# compass.net
KiCad netlist of a schematic drawn in EAGLE
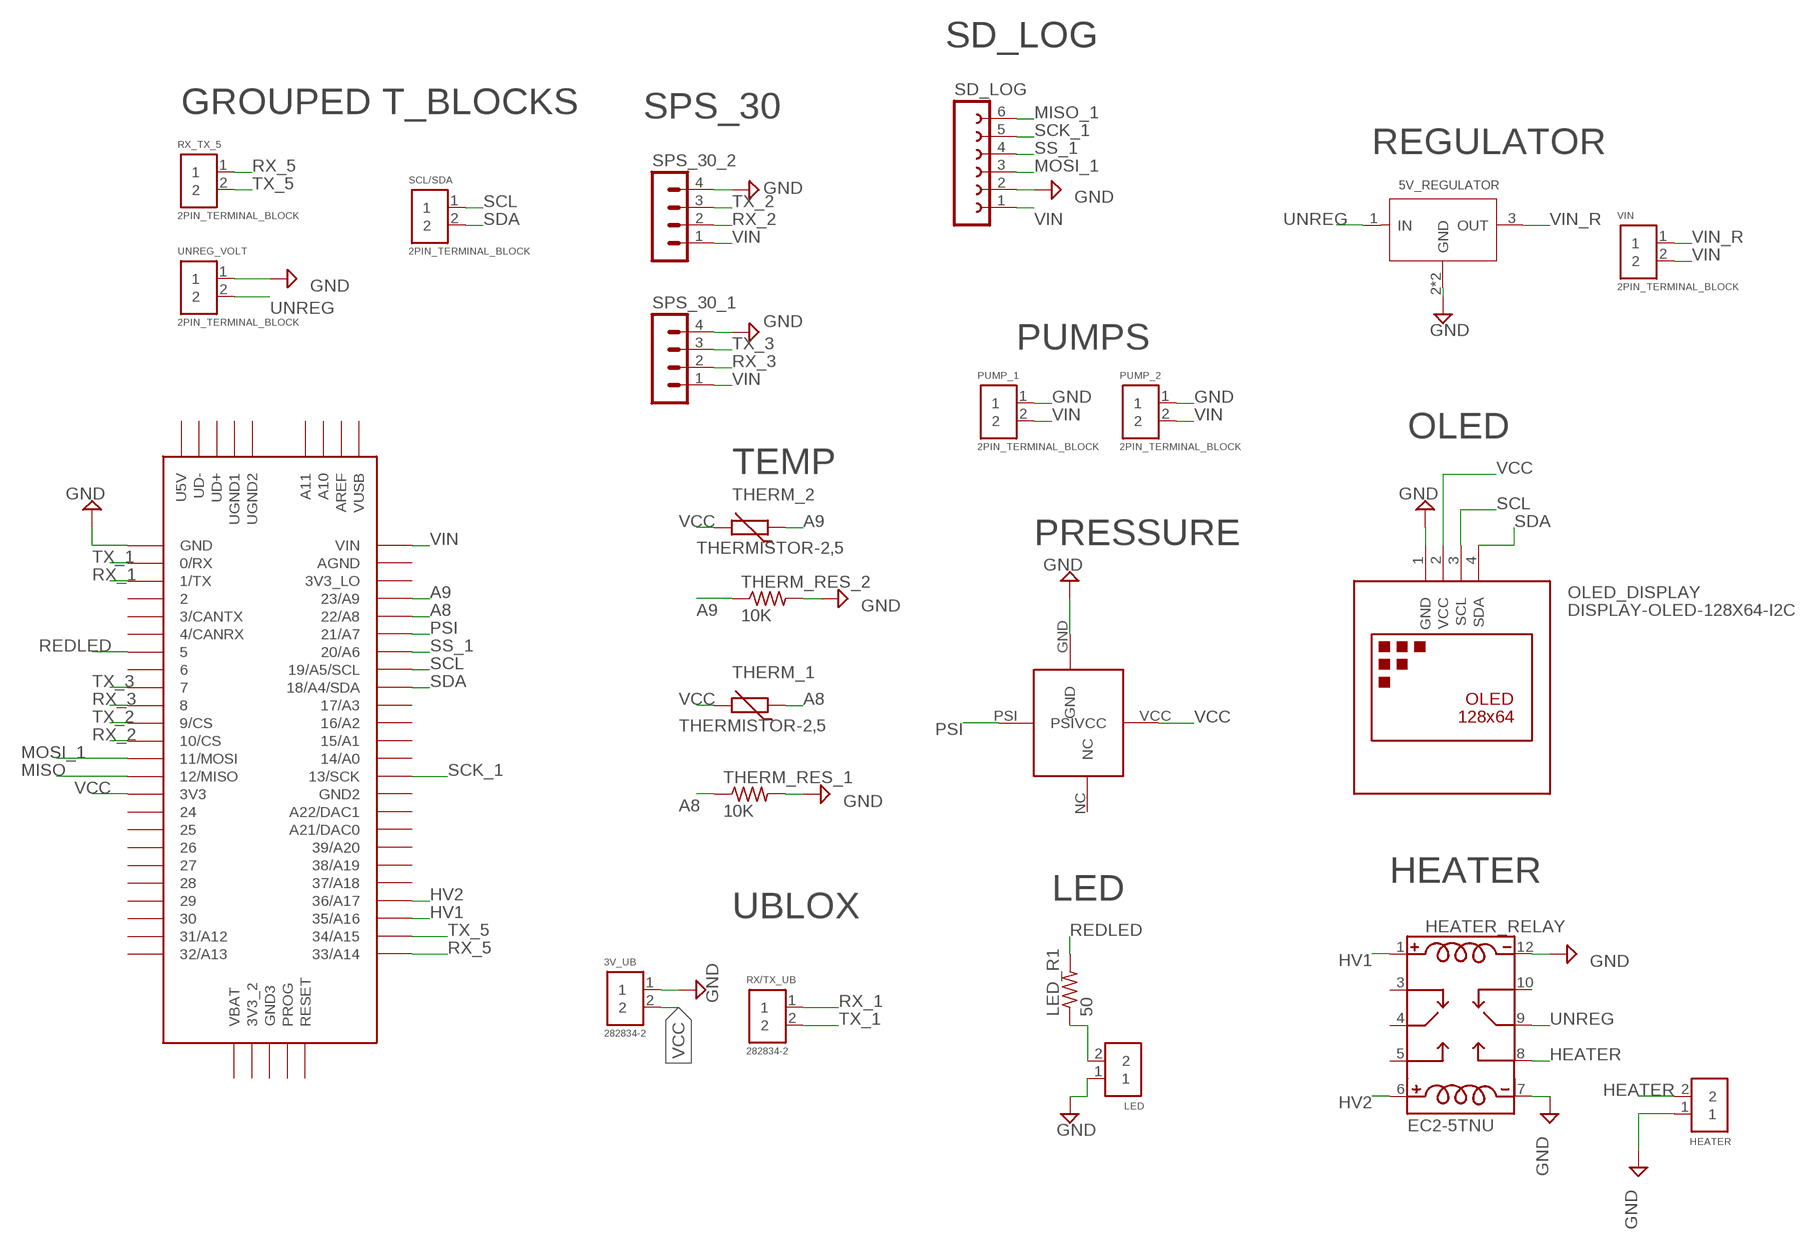
[diagram p0: schematic, sheet 1]

(export (version "E")
  (design (tool "Eeschema 10.0.6"))
  (components
    (comp (ref "3V_UB")
      (value "282834-2")
      (footprint "eagle-import:CONN_282834-2")
      (fields (field (name "DIGI-KEY_PART_NUMBER") "A98333-ND") (field (name "MF") "TE Connectivity"))
      (libsource (lib "eagle-import") (part "282834-2"))
    )
    (comp (ref "5V_REGULATOR")
      (value "PMIC-L7805CV-DG(TO-220)")
      (footprint "eagle-import:TO-220")
      (fields
        (field (name "DIGI-KEY_PART_NUMBER") "497-12404-ND")
        (field (name "MF") "STMicroelectronics")
        (field (name "MP") "L7805CV-DG")
      )
      (libsource (lib "eagle-import") (part "PMIC-L7805CV-DG(TO-220)"))
    )
    (comp (ref "HEATER")
      (value "2PIN_TERMINAL_BLOCK")
      (footprint "eagle-import:2PIN_TERMINAL_BLOCK")
      (fields
        (field (name "COMMENT") "282834-2")
        (field (name "DIGI-KEY_PART_NUMBER") "A98333-ND")
        (field (name "MF") "TE Connectivity")
      )
      (libsource (lib "eagle-import") (part "2PIN_TERMINAL_BLOCK"))
    )
    (comp (ref "HEATER_RELAY")
      (value "EC2-5TNU")
      (footprint "eagle-import:RELAY_EC2-5TNU")
      (fields (field (name "MF") "KEMET"))
      (libsource (lib "eagle-import") (part "EC2-5TNU"))
    )
    (comp (ref "LED")
      (value "282834-2")
      (footprint "eagle-import:CONN_282834-2")
      (fields (field (name "DIGI-KEY_PART_NUMBER") "A98333-ND") (field (name "MF") "TE Connectivity"))
      (libsource (lib "eagle-import") (part "282834-2"))
    )
    (comp (ref "LED_R1")
      (value "50")
      (footprint "eagle-import:0204_7")
      (libsource (lib "eagle-import") (part "resistor_348_R-US_0204/7"))
    )
    (comp (ref "OLED_DISPLAY")
      (value "DISPLAY-OLED-128X64-I2C")
      (footprint "eagle-import:DISPLAY-OLED-128X64-I2C")
      (libsource (lib "eagle-import") (part "DISPLAY-OLED-128X64-I2C"))
    )
    (comp (ref "PRESSURE_SENSOR")
      (value "SSCSANN015PAAA5")
      (footprint "eagle-import:SSCSANN015PAAA5")
      (libsource (lib "eagle-import") (part "SSCSANN015PAAA5"))
    )
    (comp (ref "PUMP_1")
      (value "2PIN_TERMINAL_BLOCK")
      (footprint "eagle-import:2PIN_TERMINAL_BLOCK")
      (fields
        (field (name "COMMENT") "282834-2")
        (field (name "DIGI-KEY_PART_NUMBER") "A98333-ND")
        (field (name "MF") "TE Connectivity")
      )
      (libsource (lib "eagle-import") (part "2PIN_TERMINAL_BLOCK"))
    )
    (comp (ref "PUMP_2")
      (value "2PIN_TERMINAL_BLOCK")
      (footprint "eagle-import:2PIN_TERMINAL_BLOCK")
      (fields
        (field (name "COMMENT") "282834-2")
        (field (name "DIGI-KEY_PART_NUMBER") "A98333-ND")
        (field (name "MF") "TE Connectivity")
      )
      (libsource (lib "eagle-import") (part "2PIN_TERMINAL_BLOCK"))
    )
    (comp (ref "RX/TX_UB")
      (value "282834-2")
      (footprint "eagle-import:CONN_282834-2")
      (fields (field (name "DIGI-KEY_PART_NUMBER") "A98333-ND") (field (name "MF") "TE Connectivity"))
      (libsource (lib "eagle-import") (part "282834-2"))
    )
    (comp (ref "RX_TX_5")
      (value "2PIN_TERMINAL_BLOCK")
      (footprint "eagle-import:2PIN_TERMINAL_BLOCK")
      (fields
        (field (name "COMMENT") "282834-2")
        (field (name "DIGI-KEY_PART_NUMBER") "A98333-ND")
        (field (name "MF") "TE Connectivity")
      )
      (libsource (lib "eagle-import") (part "2PIN_TERMINAL_BLOCK"))
    )
    (comp (ref "SCL/SDA")
      (value "2PIN_TERMINAL_BLOCK")
      (footprint "eagle-import:2PIN_TERMINAL_BLOCK")
      (fields
        (field (name "COMMENT") "282834-2")
        (field (name "DIGI-KEY_PART_NUMBER") "A98333-ND")
        (field (name "MF") "TE Connectivity")
      )
      (libsource (lib "eagle-import") (part "2PIN_TERMINAL_BLOCK"))
    )
    (comp (ref "SD_LOG")
      (value "FE06-1")
      (footprint "eagle-import:FE06")
      (libsource (lib "eagle-import") (part "FE06-1"))
    )
    (comp (ref "SPS_30_1")
      (value "MA04-1")
      (footprint "eagle-import:MA04-1")
      (libsource (lib "eagle-import") (part "MA04-1"))
    )
    (comp (ref "SPS_30_2")
      (value "MA04-1")
      (footprint "eagle-import:MA04-1")
      (libsource (lib "eagle-import") (part "MA04-1"))
    )
    (comp (ref "THERM_1")
      (value "THERMISTOR-2,5")
      (footprint "eagle-import:RS-2,5")
      (libsource (lib "eagle-import") (part "THERMISTOR-2,5"))
    )
    (comp (ref "THERM_2")
      (value "THERMISTOR-2,5")
      (footprint "eagle-import:RS-2,5")
      (libsource (lib "eagle-import") (part "THERMISTOR-2,5"))
    )
    (comp (ref "THERM_RES_1")
      (value "10K")
      (footprint "eagle-import:0204_7")
      (libsource (lib "eagle-import") (part "R-US_0204/7"))
    )
    (comp (ref "THERM_RES_2")
      (value "10K")
      (footprint "eagle-import:0204_7")
      (libsource (lib "eagle-import") (part "R-US_0204/7"))
    )
    (comp (ref "U$1")
      (value "TEENSY_3.5/3.6")
      (footprint "eagle-import:TEENSY_3.5_3.6")
      (libsource (lib "eagle-import") (part "TEENSY_3.5/3.6"))
    )
    (comp (ref "UNREG_VOLT")
      (value "2PIN_TERMINAL_BLOCK")
      (footprint "eagle-import:2PIN_TERMINAL_BLOCK")
      (fields
        (field (name "COMMENT") "282834-2")
        (field (name "DIGI-KEY_PART_NUMBER") "A98333-ND")
        (field (name "MF") "TE Connectivity")
      )
      (libsource (lib "eagle-import") (part "2PIN_TERMINAL_BLOCK"))
    )
    (comp (ref "VIN")
      (value "2PIN_TERMINAL_BLOCK")
      (footprint "eagle-import:2PIN_TERMINAL_BLOCK")
      (fields
        (field (name "COMMENT") "282834-2")
        (field (name "DIGI-KEY_PART_NUMBER") "A98333-ND")
        (field (name "MF") "TE Connectivity")
      )
      (libsource (lib "eagle-import") (part "2PIN_TERMINAL_BLOCK"))
    )
  )
  (nets
    (net (code "1") (name "/A8") (class "Default")
      (node (ref "THERM_1") (pin "1") (pinfunction "1_1") (pintype "passive"))
      (node (ref "THERM_RES_1") (pin "1") (pinfunction "1_1") (pintype "passive"))
      (node (ref "U$1") (pin "22/A8") (pinfunction "22/A8_22/A8") (pintype "bidirectional"))
    )
    (net (code "2") (name "/A9") (class "Default")
      (node (ref "THERM_2") (pin "1") (pinfunction "1_1") (pintype "passive"))
      (node (ref "THERM_RES_2") (pin "1") (pinfunction "1_1") (pintype "passive"))
      (node (ref "U$1") (pin "23/A9") (pinfunction "23/A9_23/A9") (pintype "bidirectional"))
    )
    (net (code "3") (name "/HEATER") (class "Default")
      (node (ref "HEATER") (pin "2") (pinfunction "2_2") (pintype "passive"))
      (node (ref "HEATER_RELAY") (pin "8") (pinfunction "NO_8") (pintype "passive"))
    )
    (net (code "4") (name "/HV1") (class "Default")
      (node (ref "HEATER_RELAY") (pin "1") (pinfunction "C1_1") (pintype "passive"))
      (node (ref "U$1") (pin "35/A16") (pinfunction "35/A16_35/A16") (pintype "bidirectional"))
    )
    (net (code "5") (name "/HV2") (class "Default")
      (node (ref "HEATER_RELAY") (pin "6") (pinfunction "C3_6") (pintype "passive"))
      (node (ref "U$1") (pin "36/A17") (pinfunction "36/A17_36/A17") (pintype "bidirectional"))
    )
    (net (code "6") (name "/MISO") (class "Default")
      (node (ref "U$1") (pin "12/MISO") (pinfunction "12/MISO_12/MISO") (pintype "bidirectional"))
    )
    (net (code "7") (name "/MISO_1") (class "Default")
      (node (ref "SD_LOG") (pin "6") (pinfunction "6_6") (pintype "passive"))
    )
    (net (code "8") (name "/MOSI_1") (class "Default")
      (node (ref "SD_LOG") (pin "3") (pinfunction "3_3") (pintype "passive"))
      (node (ref "U$1") (pin "11/MOSI") (pinfunction "11/MOSI_11/MOSI") (pintype "bidirectional"))
    )
    (net (code "9") (name "/PSI") (class "Default")
      (node (ref "PRESSURE_SENSOR") (pin "PSI") (pinfunction "PSI_PSI") (pintype "bidirectional"))
      (node (ref "U$1") (pin "21/A7") (pinfunction "21/A7_21/A7") (pintype "bidirectional"))
    )
    (net (code "10") (name "/REDLED") (class "Default")
      (node (ref "LED_R1") (pin "2") (pinfunction "2_2") (pintype "passive"))
      (node (ref "U$1") (pin "5") (pinfunction "5_5") (pintype "bidirectional"))
    )
    (net (code "11") (name "/RX_1") (class "Default")
      (node (ref "RX/TX_UB") (pin "1") (pinfunction "1_1") (pintype "passive"))
      (node (ref "U$1") (pin "1/TX") (pinfunction "1/TX_1/TX") (pintype "bidirectional"))
    )
    (net (code "12") (name "/RX_2") (class "Default")
      (node (ref "SPS_30_2") (pin "2") (pinfunction "2_2") (pintype "passive"))
      (node (ref "U$1") (pin "10/CS") (pinfunction "10/CS_10/CS") (pintype "bidirectional"))
    )
    (net (code "13") (name "/RX_3") (class "Default")
      (node (ref "SPS_30_1") (pin "2") (pinfunction "2_2") (pintype "passive"))
      (node (ref "U$1") (pin "8") (pinfunction "8_8") (pintype "bidirectional"))
    )
    (net (code "14") (name "/RX_5") (class "Default")
      (node (ref "RX_TX_5") (pin "1") (pinfunction "1_1") (pintype "passive"))
      (node (ref "U$1") (pin "33/A14") (pinfunction "33/A14_33/A14") (pintype "bidirectional"))
    )
    (net (code "15") (name "/SCK_1") (class "Default")
      (node (ref "SD_LOG") (pin "5") (pinfunction "5_5") (pintype "passive"))
      (node (ref "U$1") (pin "13/SCK") (pinfunction "13/SCK_13/SCK") (pintype "bidirectional"))
    )
    (net (code "16") (name "/SCL") (class "Default")
      (node (ref "OLED_DISPLAY") (pin "3") (pinfunction "SCL_3") (pintype "bidirectional"))
      (node (ref "SCL/SDA") (pin "1") (pinfunction "1_1") (pintype "passive"))
      (node (ref "U$1") (pin "19/A5/SCL") (pinfunction "19/A5/SCL_19/A5/SCL") (pintype "bidirectional"))
    )
    (net (code "17") (name "/SDA") (class "Default")
      (node (ref "OLED_DISPLAY") (pin "4") (pinfunction "SDA_4") (pintype "bidirectional"))
      (node (ref "SCL/SDA") (pin "2") (pinfunction "2_2") (pintype "passive"))
      (node (ref "U$1") (pin "18/A4/SDA") (pinfunction "18/A4/SDA_18/A4/SDA") (pintype "bidirectional"))
    )
    (net (code "18") (name "/SS_1") (class "Default")
      (node (ref "SD_LOG") (pin "4") (pinfunction "4_4") (pintype "passive"))
      (node (ref "U$1") (pin "20/A6") (pinfunction "20/A6_20/A6") (pintype "bidirectional"))
    )
    (net (code "19") (name "/TX_1") (class "Default")
      (node (ref "RX/TX_UB") (pin "2") (pinfunction "2_2") (pintype "passive"))
      (node (ref "U$1") (pin "0/RX") (pinfunction "0/RX_0/RX") (pintype "bidirectional"))
    )
    (net (code "20") (name "/TX_2") (class "Default")
      (node (ref "SPS_30_2") (pin "3") (pinfunction "3_3") (pintype "passive"))
      (node (ref "U$1") (pin "9/CS") (pinfunction "9/CS_9/CS") (pintype "bidirectional"))
    )
    (net (code "21") (name "/TX_3") (class "Default")
      (node (ref "SPS_30_1") (pin "3") (pinfunction "3_3") (pintype "passive"))
      (node (ref "U$1") (pin "7") (pinfunction "7_7") (pintype "bidirectional"))
    )
    (net (code "22") (name "/TX_5") (class "Default")
      (node (ref "RX_TX_5") (pin "2") (pinfunction "2_2") (pintype "passive"))
      (node (ref "U$1") (pin "34/A15") (pinfunction "34/A15_34/A15") (pintype "bidirectional"))
    )
    (net (code "23") (name "/UNREG") (class "Default")
      (node (ref "5V_REGULATOR") (pin "1") (pinfunction "IN_1") (pintype "bidirectional"))
      (node (ref "HEATER_RELAY") (pin "9") (pinfunction "M_9") (pintype "passive"))
      (node (ref "UNREG_VOLT") (pin "2") (pinfunction "2_2") (pintype "passive"))
    )
    (net (code "24") (name "/VIN") (class "Default")
      (node (ref "PUMP_1") (pin "2") (pinfunction "2_2") (pintype "passive"))
      (node (ref "PUMP_2") (pin "2") (pinfunction "2_2") (pintype "passive"))
      (node (ref "SD_LOG") (pin "1") (pinfunction "1_1") (pintype "passive"))
      (node (ref "SPS_30_1") (pin "1") (pinfunction "1_1") (pintype "passive"))
      (node (ref "SPS_30_2") (pin "1") (pinfunction "1_1") (pintype "passive"))
      (node (ref "U$1") (pin "VIN") (pinfunction "VIN_VIN") (pintype "bidirectional"))
      (node (ref "VIN") (pin "2") (pinfunction "2_2") (pintype "passive"))
    )
    (net (code "25") (name "/VIN_R") (class "Default")
      (node (ref "5V_REGULATOR") (pin "3") (pinfunction "OUT_3") (pintype "bidirectional"))
      (node (ref "VIN") (pin "1") (pinfunction "1_1") (pintype "passive"))
    )
    (net (code "26") (name "GND") (class "Default")
      (node (ref "3V_UB") (pin "1") (pinfunction "1_1") (pintype "passive"))
      (node (ref "5V_REGULATOR") (pin "2") (pinfunction "GND_2") (pintype "bidirectional"))
      (node (ref "5V_REGULATOR") (pin "HEAT") (pinfunction "GND_HEAT") (pintype "bidirectional"))
      (node (ref "HEATER") (pin "1") (pinfunction "1_1") (pintype "passive"))
      (node (ref "HEATER_RELAY") (pin "12") (pinfunction "C2_12") (pintype "passive"))
      (node (ref "HEATER_RELAY") (pin "7") (pinfunction "C4_7") (pintype "passive"))
      (node (ref "LED") (pin "1") (pinfunction "1_1") (pintype "passive"))
      (node (ref "OLED_DISPLAY") (pin "1") (pinfunction "GND_1") (pintype "power_in"))
      (node (ref "PRESSURE_SENSOR") (pin "GND") (pinfunction "GND_GND") (pintype "bidirectional"))
      (node (ref "PUMP_1") (pin "1") (pinfunction "1_1") (pintype "passive"))
      (node (ref "PUMP_2") (pin "1") (pinfunction "1_1") (pintype "passive"))
      (node (ref "SD_LOG") (pin "2") (pinfunction "2_2") (pintype "passive"))
      (node (ref "SPS_30_1") (pin "4") (pinfunction "4_4") (pintype "passive"))
      (node (ref "SPS_30_2") (pin "4") (pinfunction "4_4") (pintype "passive"))
      (node (ref "THERM_RES_1") (pin "2") (pinfunction "2_2") (pintype "passive"))
      (node (ref "THERM_RES_2") (pin "2") (pinfunction "2_2") (pintype "passive"))
      (node (ref "U$1") (pin "GND") (pinfunction "GND_GND") (pintype "bidirectional"))
      (node (ref "UNREG_VOLT") (pin "1") (pinfunction "1_1") (pintype "passive"))
    )
    (net (code "27") (name "Net-(LED-Pad2)") (class "Default")
      (node (ref "LED") (pin "2") (pinfunction "2_2") (pintype "passive"))
      (node (ref "LED_R1") (pin "1") (pinfunction "1_1") (pintype "passive"))
    )
    (net (code "28") (name "VCC") (class "Default")
      (node (ref "3V_UB") (pin "2") (pinfunction "2_2") (pintype "passive"))
      (node (ref "OLED_DISPLAY") (pin "2") (pinfunction "VCC_2") (pintype "power_in"))
      (node (ref "PRESSURE_SENSOR") (pin "VCC") (pinfunction "VCC_VCC") (pintype "bidirectional"))
      (node (ref "THERM_1") (pin "2") (pinfunction "2_2") (pintype "passive"))
      (node (ref "THERM_2") (pin "2") (pinfunction "2_2") (pintype "passive"))
      (node (ref "U$1") (pin "3V3") (pinfunction "3V3_3V3") (pintype "bidirectional"))
    )
    (net (code "29") (name "unconnected-(HEATER_RELAY-M1-Pad4)") (class "Default")
      (node (ref "HEATER_RELAY") (pin "4") (pinfunction "M1_4") (pintype "passive"))
    )
    (net (code "30") (name "unconnected-(HEATER_RELAY-NC-Pad10)") (class "Default")
      (node (ref "HEATER_RELAY") (pin "10") (pinfunction "NC_10") (pintype "passive"))
    )
    (net (code "31") (name "unconnected-(HEATER_RELAY-NC1-Pad3)") (class "Default")
      (node (ref "HEATER_RELAY") (pin "3") (pinfunction "NC1_3") (pintype "passive"))
    )
    (net (code "32") (name "unconnected-(HEATER_RELAY-NO1-Pad5)") (class "Default")
      (node (ref "HEATER_RELAY") (pin "5") (pinfunction "NO1_5") (pintype "passive"))
    )
    (net (code "33") (name "unconnected-(PRESSURE_SENSOR-PadNC)") (class "Default")
      (node (ref "PRESSURE_SENSOR") (pin "NC") (pinfunction "NC_NC") (pintype "bidirectional"))
    )
    (net (code "34") (name "unconnected-(U$1-A21{slash}DAC0-Pad21{slash}DAC0)") (class "Default")
      (node (ref "U$1") (pin "21/DAC0") (pinfunction "A21/DAC0_21/DAC0") (pintype "bidirectional"))
    )
    (net (code "35") (name "unconnected-(U$1-Pad2)") (class "Default")
      (node (ref "U$1") (pin "2") (pinfunction "2_2") (pintype "bidirectional"))
    )
    (net (code "36") (name "unconnected-(U$1-Pad3V3_2)") (class "Default")
      (node (ref "U$1") (pin "3V3_2") (pinfunction "3V3_2_3V3_2") (pintype "bidirectional"))
    )
    (net (code "37") (name "unconnected-(U$1-Pad3V3_LO)") (class "Default")
      (node (ref "U$1") (pin "3V3_LO") (pinfunction "3V3_LO_3V3_LO") (pintype "bidirectional"))
    )
    (net (code "38") (name "unconnected-(U$1-Pad3{slash}CANTX)") (class "Default")
      (node (ref "U$1") (pin "3/CANTX") (pinfunction "3/CANTX_3/CANTX") (pintype "bidirectional"))
    )
    (net (code "39") (name "unconnected-(U$1-Pad4{slash}CANRX)") (class "Default")
      (node (ref "U$1") (pin "4/CANRX") (pinfunction "4/CANRX_4/CANRX") (pintype "bidirectional"))
    )
    (net (code "40") (name "unconnected-(U$1-Pad6)") (class "Default")
      (node (ref "U$1") (pin "6") (pinfunction "6_6") (pintype "bidirectional"))
    )
    (net (code "41") (name "unconnected-(U$1-Pad14{slash}A0)") (class "Default")
      (node (ref "U$1") (pin "14/A0") (pinfunction "14/A0_14/A0") (pintype "bidirectional"))
    )
    (net (code "42") (name "unconnected-(U$1-Pad15{slash}A1)") (class "Default")
      (node (ref "U$1") (pin "15/A1") (pinfunction "15/A1_15/A1") (pintype "bidirectional"))
    )
    (net (code "43") (name "unconnected-(U$1-Pad16{slash}A2)") (class "Default")
      (node (ref "U$1") (pin "16/A2") (pinfunction "16/A2_16/A2") (pintype "bidirectional"))
    )
    (net (code "44") (name "unconnected-(U$1-Pad17{slash}A3)") (class "Default")
      (node (ref "U$1") (pin "17/A3") (pinfunction "17/A3_17/A3") (pintype "bidirectional"))
    )
    (net (code "45") (name "unconnected-(U$1-Pad24)") (class "Default")
      (node (ref "U$1") (pin "24") (pinfunction "24_24") (pintype "bidirectional"))
    )
    (net (code "46") (name "unconnected-(U$1-Pad25)") (class "Default")
      (node (ref "U$1") (pin "25") (pinfunction "25_25") (pintype "bidirectional"))
    )
    (net (code "47") (name "unconnected-(U$1-Pad26)") (class "Default")
      (node (ref "U$1") (pin "26") (pinfunction "26_26") (pintype "bidirectional"))
    )
    (net (code "48") (name "unconnected-(U$1-Pad27)") (class "Default")
      (node (ref "U$1") (pin "27") (pinfunction "27_27") (pintype "bidirectional"))
    )
    (net (code "49") (name "unconnected-(U$1-Pad28)") (class "Default")
      (node (ref "U$1") (pin "28") (pinfunction "28_28") (pintype "bidirectional"))
    )
    (net (code "50") (name "unconnected-(U$1-Pad29)") (class "Default")
      (node (ref "U$1") (pin "29") (pinfunction "29_29") (pintype "bidirectional"))
    )
    (net (code "51") (name "unconnected-(U$1-Pad30)") (class "Default")
      (node (ref "U$1") (pin "30") (pinfunction "30_30") (pintype "bidirectional"))
    )
    (net (code "52") (name "unconnected-(U$1-Pad31{slash}A12)") (class "Default")
      (node (ref "U$1") (pin "31/A12") (pinfunction "31/A12_31/A12") (pintype "bidirectional"))
    )
    (net (code "53") (name "unconnected-(U$1-Pad32{slash}A13)") (class "Default")
      (node (ref "U$1") (pin "32/A13") (pinfunction "32/A13_32/A13") (pintype "bidirectional"))
    )
    (net (code "54") (name "unconnected-(U$1-Pad37{slash}A18)") (class "Default")
      (node (ref "U$1") (pin "37/A18") (pinfunction "37/A18_37/A18") (pintype "bidirectional"))
    )
    (net (code "55") (name "unconnected-(U$1-Pad38{slash}A19)") (class "Default")
      (node (ref "U$1") (pin "38/A19") (pinfunction "38/A19_38/A19") (pintype "bidirectional"))
    )
    (net (code "56") (name "unconnected-(U$1-Pad39{slash}A20)") (class "Default")
      (node (ref "U$1") (pin "39/A20") (pinfunction "39/A20_39/A20") (pintype "bidirectional"))
    )
    (net (code "57") (name "unconnected-(U$1-PadA10)") (class "Default")
      (node (ref "U$1") (pin "A10") (pinfunction "A10_A10") (pintype "bidirectional"))
    )
    (net (code "58") (name "unconnected-(U$1-PadA11)") (class "Default")
      (node (ref "U$1") (pin "A11") (pinfunction "A11_A11") (pintype "bidirectional"))
    )
    (net (code "59") (name "unconnected-(U$1-PadA22{slash}DAC1)") (class "Default")
      (node (ref "U$1") (pin "A22/DAC1") (pinfunction "A22/DAC1_A22/DAC1") (pintype "bidirectional"))
    )
    (net (code "60") (name "unconnected-(U$1-PadAGND)") (class "Default")
      (node (ref "U$1") (pin "AGND") (pinfunction "AGND_AGND") (pintype "bidirectional"))
    )
    (net (code "61") (name "unconnected-(U$1-PadAREF)") (class "Default")
      (node (ref "U$1") (pin "AREF") (pinfunction "AREF_AREF") (pintype "bidirectional"))
    )
    (net (code "62") (name "unconnected-(U$1-PadGND2)") (class "Default")
      (node (ref "U$1") (pin "GND2") (pinfunction "GND2_GND2") (pintype "bidirectional"))
    )
    (net (code "63") (name "unconnected-(U$1-PadGND3)") (class "Default")
      (node (ref "U$1") (pin "GND3") (pinfunction "GND3_GND3") (pintype "bidirectional"))
    )
    (net (code "64") (name "unconnected-(U$1-PadPROG)") (class "Default")
      (node (ref "U$1") (pin "PROG") (pinfunction "PROG_PROG") (pintype "bidirectional"))
    )
    (net (code "65") (name "unconnected-(U$1-PadRESET)") (class "Default")
      (node (ref "U$1") (pin "RESET") (pinfunction "RESET_RESET") (pintype "bidirectional"))
    )
    (net (code "66") (name "unconnected-(U$1-PadU5V)") (class "Default")
      (node (ref "U$1") (pin "U5V") (pinfunction "U5V_U5V") (pintype "bidirectional"))
    )
    (net (code "67") (name "unconnected-(U$1-PadUD+)") (class "Default")
      (node (ref "U$1") (pin "UD+") (pinfunction "UD+_UD+") (pintype "bidirectional"))
    )
    (net (code "68") (name "unconnected-(U$1-PadUD-)") (class "Default")
      (node (ref "U$1") (pin "UD-") (pinfunction "UD-_UD-") (pintype "bidirectional"))
    )
    (net (code "69") (name "unconnected-(U$1-PadUGND1)") (class "Default")
      (node (ref "U$1") (pin "UGND1") (pinfunction "UGND1_UGND1") (pintype "bidirectional"))
    )
    (net (code "70") (name "unconnected-(U$1-PadUGND2)") (class "Default")
      (node (ref "U$1") (pin "UGND2") (pinfunction "UGND2_UGND2") (pintype "bidirectional"))
    )
    (net (code "71") (name "unconnected-(U$1-PadVBAT)") (class "Default")
      (node (ref "U$1") (pin "VBAT") (pinfunction "VBAT_VBAT") (pintype "bidirectional"))
    )
    (net (code "72") (name "unconnected-(U$1-PadVUSB)") (class "Default")
      (node (ref "U$1") (pin "VUSB") (pinfunction "VUSB_VUSB") (pintype "bidirectional"))
    )
  )
)
